# Main.net
KiCad netlist of a schematic drawn in Altium Designer
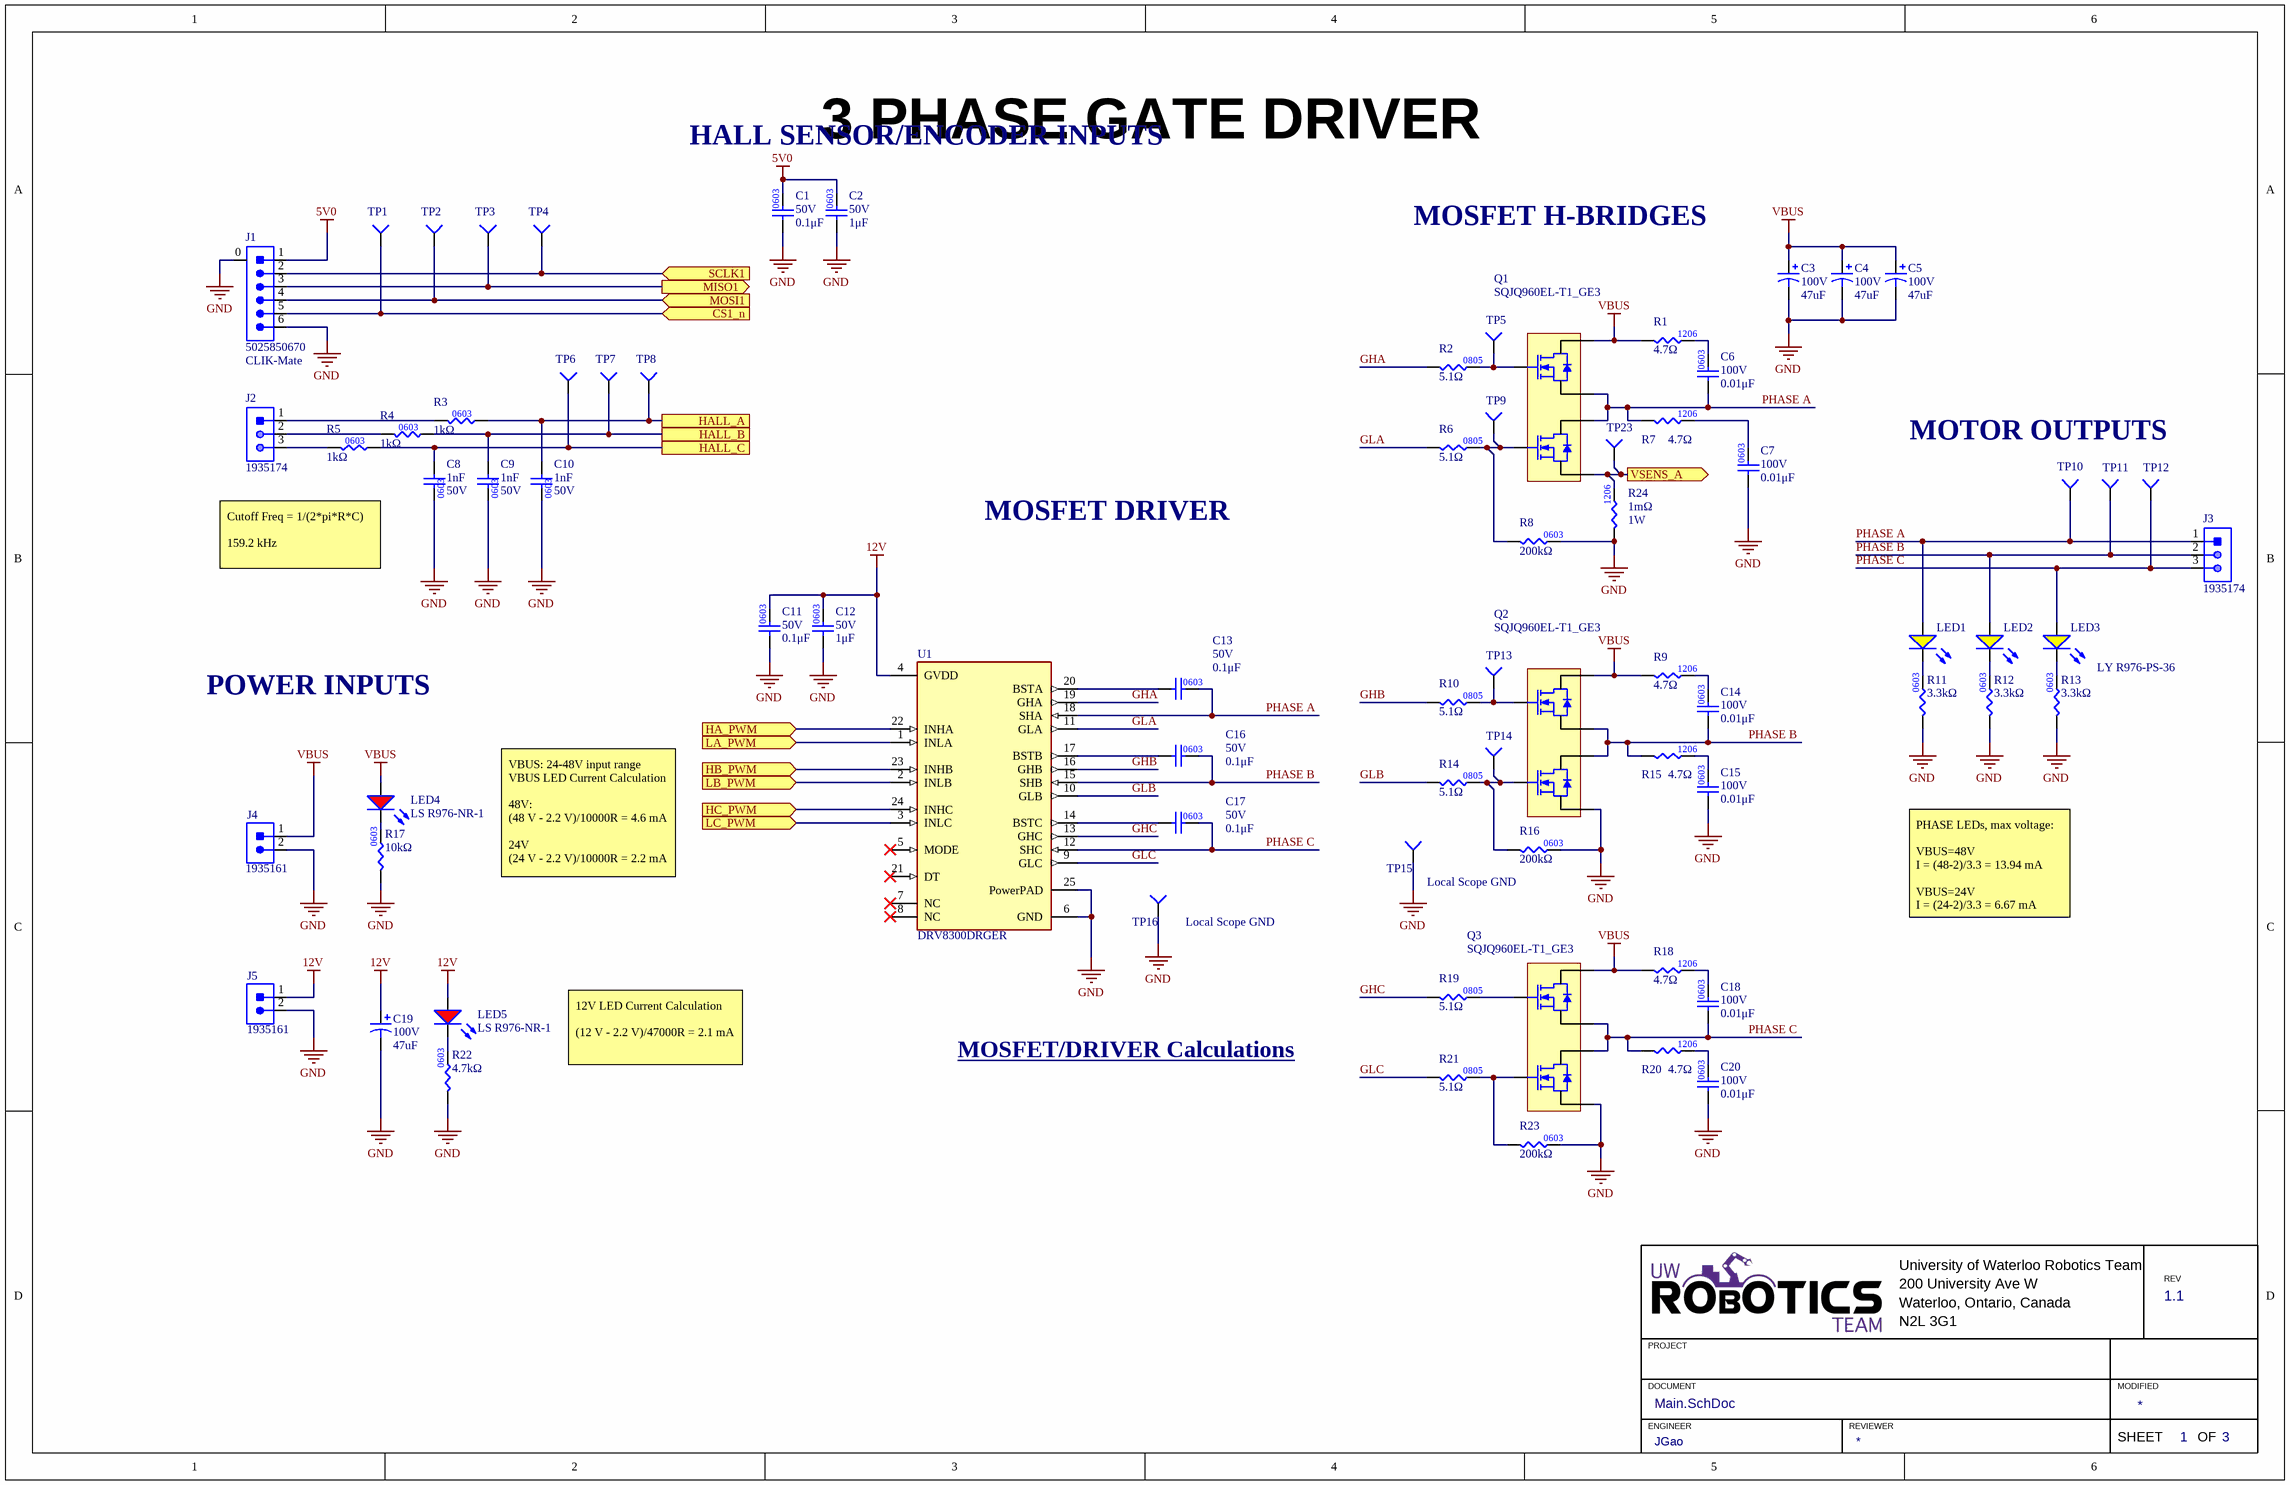
[diagram p0: Main.SchDoc]

(export (version "E")
  (design (tool "Eeschema 10.0.6"))
  (components
    (comp (ref "C1")
      (value "0.1μF")
      (footprint "CAP0603")
      (description "CAP CER 0.1UF 50V X7R 0603")
      (fields (field (name "VOLTAGE RATING") "50V") (field (name "Comment") "CAP_0.1uF_50V_0603"))
      (libsource (lib "UWRT_Schematic_Library_2020") (part "CAP_0.1uF_50V_0603"))
    )
    (comp (ref "C2")
      (value "1μF")
      (footprint "CAP0603")
      (description "CAP CER 1UF 50V X6S 0603")
      (fields (field (name "VOLTAGE RATING") "50V") (field (name "Comment") "CAP_1uF_50V_0603"))
      (libsource (lib "UWRT_Schematic_Library_2020") (part "CAP_1uF_50V_0603"))
    )
    (comp (ref "C3")
      (value "CAP_47uF_100V_ALUM")
      (footprint "RADIAL_CORNELL_D")
      (fields
        (field (name "MANUFACTURER") "Nichicon")
        (field (name "MANUFACTURER PART NUMBER") "UCD2A470MNQ1MS")
        (field (name "VOLTAGE RATING") "100V")
        (field (name "CAPACITANCE") "47uF")
      )
      (libsource (lib "UWRT_Schematic_Library_2020") (part "CAP_47uF_100V_ALUM"))
    )
    (comp (ref "C4")
      (value "CAP_47uF_100V_ALUM")
      (footprint "RADIAL_CORNELL_D")
      (fields
        (field (name "MANUFACTURER") "Nichicon")
        (field (name "MANUFACTURER PART NUMBER") "UCD2A470MNQ1MS")
        (field (name "VOLTAGE RATING") "100V")
        (field (name "CAPACITANCE") "47uF")
      )
      (libsource (lib "UWRT_Schematic_Library_2020") (part "CAP_47uF_100V_ALUM"))
    )
    (comp (ref "C5")
      (value "CAP_47uF_100V_ALUM")
      (footprint "RADIAL_CORNELL_D")
      (fields
        (field (name "MANUFACTURER") "Nichicon")
        (field (name "MANUFACTURER PART NUMBER") "UCD2A470MNQ1MS")
        (field (name "VOLTAGE RATING") "100V")
        (field (name "CAPACITANCE") "47uF")
      )
      (libsource (lib "UWRT_Schematic_Library_2020") (part "CAP_47uF_100V_ALUM"))
    )
    (comp (ref "C6")
      (value "0.01μF")
      (footprint "CAP0603")
      (description "CAP CER 0.01uF 100V X7R 0603")
      (fields (field (name "VOLTAGE RATING") "100V") (field (name "Comment") "CAP_0.01uF_100V_0603"))
      (libsource (lib "UWRT_Schematic_Library_2020") (part "CAP_0.01uF_100V_0603"))
    )
    (comp (ref "C7")
      (value "0.01μF")
      (footprint "CAP0603")
      (description "CAP CER 0.01uF 100V X7R 0603")
      (fields (field (name "VOLTAGE RATING") "100V") (field (name "Comment") "CAP_0.01uF_100V_0603"))
      (libsource (lib "UWRT_Schematic_Library_2020") (part "CAP_0.01uF_100V_0603"))
    )
    (comp (ref "C8")
      (value "1nF")
      (footprint "cap0603")
      (description "CAP CER 1NF 50V X7R 0603")
      (fields
        (field (name "MANUFACTURER") "KYOCERA AVX")
        (field (name "MANUFACTURER PART NUMBER") "06035C102KAT2A")
        (field (name "VOLTAGE RATING") "50V")
      )
      (libsource (lib "UWRT_Schematic_Library_2020") (part "CAP_1nF_50V_0603_XR7"))
    )
    (comp (ref "C9")
      (value "1nF")
      (footprint "cap0603")
      (description "CAP CER 1NF 50V X7R 0603")
      (fields
        (field (name "MANUFACTURER") "KYOCERA AVX")
        (field (name "MANUFACTURER PART NUMBER") "06035C102KAT2A")
        (field (name "VOLTAGE RATING") "50V")
      )
      (libsource (lib "UWRT_Schematic_Library_2020") (part "CAP_1nF_50V_0603_XR7"))
    )
    (comp (ref "C10")
      (value "1nF")
      (footprint "cap0603")
      (description "CAP CER 1NF 50V X7R 0603")
      (fields
        (field (name "MANUFACTURER") "KYOCERA AVX")
        (field (name "MANUFACTURER PART NUMBER") "06035C102KAT2A")
        (field (name "VOLTAGE RATING") "50V")
      )
      (libsource (lib "UWRT_Schematic_Library_2020") (part "CAP_1nF_50V_0603_XR7"))
    )
    (comp (ref "C11")
      (value "0.1μF")
      (footprint "CAP0603")
      (description "CAP CER 0.1UF 50V X7R 0603")
      (fields (field (name "VOLTAGE RATING") "50V") (field (name "Comment") "CAP_0.1uF_50V_0603"))
      (libsource (lib "UWRT_Schematic_Library_2020") (part "CAP_0.1uF_50V_0603"))
    )
    (comp (ref "C12")
      (value "1μF")
      (footprint "CAP0603")
      (description "CAP CER 1UF 50V X6S 0603")
      (fields (field (name "VOLTAGE RATING") "50V") (field (name "Comment") "CAP_1uF_50V_0603"))
      (libsource (lib "UWRT_Schematic_Library_2020") (part "CAP_1uF_50V_0603"))
    )
    (comp (ref "C13")
      (value "0.1μF")
      (footprint "CAP0603")
      (description "CAP CER 0.1UF 50V X7R 0603")
      (fields (field (name "VOLTAGE RATING") "50V") (field (name "Comment") "CAP_0.1uF_50V_0603"))
      (libsource (lib "UWRT_Schematic_Library_2020") (part "CAP_0.1uF_50V_0603"))
    )
    (comp (ref "C14")
      (value "0.01μF")
      (footprint "CAP0603")
      (description "CAP CER 0.01uF 100V X7R 0603")
      (fields (field (name "VOLTAGE RATING") "100V") (field (name "Comment") "CAP_0.01uF_100V_0603"))
      (libsource (lib "UWRT_Schematic_Library_2020") (part "CAP_0.01uF_100V_0603"))
    )
    (comp (ref "C15")
      (value "0.01μF")
      (footprint "CAP0603")
      (description "CAP CER 0.01uF 100V X7R 0603")
      (fields (field (name "VOLTAGE RATING") "100V") (field (name "Comment") "CAP_0.01uF_100V_0603"))
      (libsource (lib "UWRT_Schematic_Library_2020") (part "CAP_0.01uF_100V_0603"))
    )
    (comp (ref "C16")
      (value "0.1μF")
      (footprint "CAP0603")
      (description "CAP CER 0.1UF 50V X7R 0603")
      (fields (field (name "VOLTAGE RATING") "50V") (field (name "Comment") "CAP_0.1uF_50V_0603"))
      (libsource (lib "UWRT_Schematic_Library_2020") (part "CAP_0.1uF_50V_0603"))
    )
    (comp (ref "C17")
      (value "0.1μF")
      (footprint "CAP0603")
      (description "CAP CER 0.1UF 50V X7R 0603")
      (fields (field (name "VOLTAGE RATING") "50V") (field (name "Comment") "CAP_0.1uF_50V_0603"))
      (libsource (lib "UWRT_Schematic_Library_2020") (part "CAP_0.1uF_50V_0603"))
    )
    (comp (ref "C18")
      (value "0.01μF")
      (footprint "CAP0603")
      (description "CAP CER 0.01uF 100V X7R 0603")
      (fields (field (name "VOLTAGE RATING") "100V") (field (name "Comment") "CAP_0.01uF_100V_0603"))
      (libsource (lib "UWRT_Schematic_Library_2020") (part "CAP_0.01uF_100V_0603"))
    )
    (comp (ref "C19")
      (value "CAP_47uF_100V_ALUM")
      (footprint "RADIAL_CORNELL_D")
      (fields
        (field (name "MANUFACTURER") "Nichicon")
        (field (name "MANUFACTURER PART NUMBER") "UCD2A470MNQ1MS")
        (field (name "VOLTAGE RATING") "100V")
        (field (name "CAPACITANCE") "47uF")
      )
      (libsource (lib "UWRT_Schematic_Library_2020") (part "CAP_47uF_100V_ALUM"))
    )
    (comp (ref "C20")
      (value "0.01μF")
      (footprint "CAP0603")
      (description "CAP CER 0.01uF 100V X7R 0603")
      (fields (field (name "VOLTAGE RATING") "100V") (field (name "Comment") "CAP_0.01uF_100V_0603"))
      (libsource (lib "UWRT_Schematic_Library_2020") (part "CAP_0.01uF_100V_0603"))
    )
    (comp (ref "J1")
      (value "CON_6M_SM_RA_1.5mm")
      (footprint "MOLEX-5025850670")
      (description "CONN HEADER SMD RIGHT ANGLE 1.5 MM PITCH")
      (fields (field (name "MANUFACTURER PART NUMBER 1") "5025850670") (field (name "FAMILY") "CLIK-Mate"))
      (libsource (lib "UWRT_Schematic_Library_2020") (part "CON_6M_SM_RA_1.5mm"))
    )
    (comp (ref "J2")
      (value "CON_3POS_SCREW_TERM")
      (footprint "1935174")
      (description "TERM BLK 3POS SIDE ENTRY 5MM")
      (fields (field (name "MANUFACTURER PART NUMBER 1") "1935174"))
      (libsource (lib "UWRT_Schematic_Library_2020") (part "CON_3POS_SCREW_TERM"))
    )
    (comp (ref "J3")
      (value "CON_3POS_SCREW_TERM")
      (footprint "1935174")
      (description "TERM BLK 3POS SIDE ENTRY 5MM")
      (fields (field (name "MANUFACTURER PART NUMBER 1") "1935174"))
      (libsource (lib "") (part "CON_3POS_SCREW_TERM_1"))
    )
    (comp (ref "J4")
      (value "CON_2POS_SCREW_TERM")
      (footprint "1935161")
      (description "TERM BLK 2POS SIDE ENTRY 5MM")
      (fields (field (name "MANUFACTURER PART NUMBER 1") "1935161"))
      (libsource (lib "UWRT_Schematic_Library_2020") (part "CON_2POS_SCREW_TERM"))
    )
    (comp (ref "J5")
      (value "CON_2POS_SCREW_TERM")
      (footprint "1935161")
      (description "TERM BLK 2POS SIDE ENTRY 5MM")
      (fields (field (name "MANUFACTURER PART NUMBER 1") "1935161"))
      (libsource (lib "UWRT_Schematic_Library_2020") (part "CON_2POS_SCREW_TERM"))
    )
    (comp (ref "LED1")
      (value "LED_YELLOW")
      (footprint "LED_0805_YELLOW")
      (description "LED YELLOW DIFFUSED 0805 SMD")
      (fields (field (name "MANUFACTURER PART NUMBER 1") "LY R976-PS-36"))
      (libsource (lib "UWRT_Schematic_Library_2020") (part "LED_YELLOW"))
    )
    (comp (ref "LED2")
      (value "LED_YELLOW")
      (footprint "LED_0805_YELLOW")
      (description "LED YELLOW DIFFUSED 0805 SMD")
      (libsource (lib "UWRT_Schematic_Library_2020") (part "LED_YELLOW"))
    )
    (comp (ref "LED3")
      (value "LED_YELLOW")
      (footprint "LED_0805_YELLOW")
      (description "LED YELLOW DIFFUSED 0805 SMD")
      (libsource (lib "UWRT_Schematic_Library_2020") (part "LED_YELLOW"))
    )
    (comp (ref "LED4")
      (value "LED_RED")
      (footprint "LED_0805_RED")
      (description "LED RED DIFFUSED 0805 SMD")
      (fields (field (name "MANUFACTURER PART NUMBER 1") "LS R976-NR-1"))
      (libsource (lib "UWRT_Schematic_Library_2020") (part "LED_RED"))
    )
    (comp (ref "LED5")
      (value "LED_RED")
      (footprint "LED_0805_RED")
      (description "LED RED DIFFUSED 0805 SMD")
      (fields (field (name "MANUFACTURER PART NUMBER 1") "LS R976-NR-1"))
      (libsource (lib "UWRT_Schematic_Library_2020") (part "LED_RED"))
    )
    (comp (ref "Q1")
      (value "NMOS_2CH_60V_63A")
      (footprint "PowerPAK 8 x 8 Dual")
      (description "MOSFET 2 N-CH 60V POWERPAK8X8")
      (fields
        (field (name "MANUFACTURER") "Vishay")
        (field (name "MANUFACTURER PART NUMBER") "SQJQ960EL-T1_GE3")
      )
      (libsource (lib "UWRT_Schematic_Library_2020") (part "NMOS_2CH_60V_63A"))
    )
    (comp (ref "Q2")
      (value "NMOS_2CH_60V_63A")
      (footprint "PowerPAK 8 x 8 Dual")
      (description "MOSFET 2 N-CH 60V POWERPAK8X8")
      (fields
        (field (name "MANUFACTURER") "Vishay")
        (field (name "MANUFACTURER PART NUMBER") "SQJQ960EL-T1_GE3")
      )
      (libsource (lib "UWRT_Schematic_Library_2020") (part "NMOS_2CH_60V_63A"))
    )
    (comp (ref "Q3")
      (value "NMOS_2CH_60V_63A")
      (footprint "PowerPAK 8 x 8 Dual")
      (description "MOSFET 2 N-CH 60V POWERPAK8X8")
      (fields
        (field (name "MANUFACTURER") "Vishay")
        (field (name "MANUFACTURER PART NUMBER") "SQJQ960EL-T1_GE3")
      )
      (libsource (lib "UWRT_Schematic_Library_2020") (part "NMOS_2CH_60V_63A"))
    )
    (comp (ref "R1")
      (value "4.7Ω")
      (footprint "RES1206")
      (description "RES 4.7 OHM 1% 1/2W 1206")
      (fields (field (name "Comment") "RES_4.7Ω_1206_1%"))
      (libsource (lib "UWRT_Schematic_Library_2020") (part "RES_4.7Ω_1206_1%"))
    )
    (comp (ref "R2")
      (value "5.1Ω")
      (footprint "RES0805")
      (description "RES 5.1 OHM 5% 1/8W 0805")
      (fields (field (name "Comment") "RES_5.1Ω_0805_5%"))
      (libsource (lib "UWRT_Schematic_Library_2020") (part "RES_5.1Ω_0805_5%"))
    )
    (comp (ref "R3")
      (value "1kΩ")
      (footprint "RES0603")
      (description "RES 1K OHM 5% 1/10W 0603")
      (fields (field (name "Comment") "RES_1kΩ_0603_5%"))
      (libsource (lib "UWRT_Schematic_Library_2020") (part "RES_1kΩ_0603_5%"))
    )
    (comp (ref "R4")
      (value "1kΩ")
      (footprint "RES0603")
      (description "RES 1K OHM 5% 1/10W 0603")
      (fields (field (name "Comment") "RES_1kΩ_0603_5%"))
      (libsource (lib "UWRT_Schematic_Library_2020") (part "RES_1kΩ_0603_5%"))
    )
    (comp (ref "R5")
      (value "1kΩ")
      (footprint "RES0603")
      (description "RES 1K OHM 5% 1/10W 0603")
      (fields (field (name "Comment") "RES_1kΩ_0603_5%"))
      (libsource (lib "UWRT_Schematic_Library_2020") (part "RES_1kΩ_0603_5%"))
    )
    (comp (ref "R6")
      (value "5.1Ω")
      (footprint "RES0805")
      (description "RES 5.1 OHM 5% 1/8W 0805")
      (fields (field (name "Comment") "RES_5.1Ω_0805_5%"))
      (libsource (lib "UWRT_Schematic_Library_2020") (part "RES_5.1Ω_0805_5%"))
    )
    (comp (ref "R7")
      (value "4.7Ω")
      (footprint "RES1206")
      (description "RES 4.7 OHM 1% 1/2W 1206")
      (fields (field (name "Comment") "RES_4.7Ω_1206_1%"))
      (libsource (lib "UWRT_Schematic_Library_2020") (part "RES_4.7Ω_1206_1%"))
    )
    (comp (ref "R8")
      (value "200kΩ")
      (footprint "RES0603")
      (description "RES 200K OHM 5% 1/10W 0603")
      (fields (field (name "Comment") "RES_200kΩ_0603_5%"))
      (libsource (lib "UWRT_Schematic_Library_2020") (part "RES_200kΩ_0603_5%"))
    )
    (comp (ref "R9")
      (value "4.7Ω")
      (footprint "RES1206")
      (description "RES 4.7 OHM 1% 1/2W 1206")
      (fields (field (name "Comment") "RES_4.7Ω_1206_1%"))
      (libsource (lib "UWRT_Schematic_Library_2020") (part "RES_4.7Ω_1206_1%"))
    )
    (comp (ref "R10")
      (value "5.1Ω")
      (footprint "RES0805")
      (description "RES 5.1 OHM 5% 1/8W 0805")
      (fields (field (name "Comment") "RES_5.1Ω_0805_5%"))
      (libsource (lib "UWRT_Schematic_Library_2020") (part "RES_5.1Ω_0805_5%"))
    )
    (comp (ref "R11")
      (value "3.3kΩ")
      (footprint "RES0603")
      (description "RES 3.3K OHM 1% 1/10W 0603")
      (fields (field (name "Comment") "RES_3.3kΩ_0603_1%"))
      (libsource (lib "UWRT_Schematic_Library_2020") (part "RES_3.3kΩ_0603_1%"))
    )
    (comp (ref "R12")
      (value "3.3kΩ")
      (footprint "RES0603")
      (description "RES 3.3K OHM 1% 1/10W 0603")
      (fields (field (name "Comment") "RES_3.3kΩ_0603_1%"))
      (libsource (lib "UWRT_Schematic_Library_2020") (part "RES_3.3kΩ_0603_1%"))
    )
    (comp (ref "R13")
      (value "3.3kΩ")
      (footprint "RES0603")
      (description "RES 3.3K OHM 1% 1/10W 0603")
      (fields (field (name "Comment") "RES_3.3kΩ_0603_1%"))
      (libsource (lib "UWRT_Schematic_Library_2020") (part "RES_3.3kΩ_0603_1%"))
    )
    (comp (ref "R14")
      (value "5.1Ω")
      (footprint "RES0805")
      (description "RES 5.1 OHM 5% 1/8W 0805")
      (fields (field (name "Comment") "RES_5.1Ω_0805_5%"))
      (libsource (lib "UWRT_Schematic_Library_2020") (part "RES_5.1Ω_0805_5%"))
    )
    (comp (ref "R15")
      (value "4.7Ω")
      (footprint "RES1206")
      (description "RES 4.7 OHM 1% 1/2W 1206")
      (fields (field (name "Comment") "RES_4.7Ω_1206_1%"))
      (libsource (lib "UWRT_Schematic_Library_2020") (part "RES_4.7Ω_1206_1%"))
    )
    (comp (ref "R16")
      (value "200kΩ")
      (footprint "RES0603")
      (description "RES 200K OHM 5% 1/10W 0603")
      (fields (field (name "Comment") "RES_200kΩ_0603_5%"))
      (libsource (lib "UWRT_Schematic_Library_2020") (part "RES_200kΩ_0603_5%"))
    )
    (comp (ref "R17")
      (value "10kΩ")
      (footprint "RES0603")
      (description "RES 10K OHM 5% 1/10W 0603")
      (fields (field (name "Comment") "RES_10kΩ_0603_5%"))
      (libsource (lib "UWRT_Schematic_Library_2020") (part "RES_10kΩ_0603_5%"))
    )
    (comp (ref "R18")
      (value "4.7Ω")
      (footprint "RES1206")
      (description "RES 4.7 OHM 1% 1/2W 1206")
      (fields (field (name "Comment") "RES_4.7Ω_1206_1%"))
      (libsource (lib "UWRT_Schematic_Library_2020") (part "RES_4.7Ω_1206_1%"))
    )
    (comp (ref "R19")
      (value "5.1Ω")
      (footprint "RES0805")
      (description "RES 5.1 OHM 5% 1/8W 0805")
      (fields (field (name "Comment") "RES_5.1Ω_0805_5%"))
      (libsource (lib "UWRT_Schematic_Library_2020") (part "RES_5.1Ω_0805_5%"))
    )
    (comp (ref "R20")
      (value "4.7Ω")
      (footprint "RES1206")
      (description "RES 4.7 OHM 1% 1/2W 1206")
      (fields (field (name "Comment") "RES_4.7Ω_1206_1%"))
      (libsource (lib "UWRT_Schematic_Library_2020") (part "RES_4.7Ω_1206_1%"))
    )
    (comp (ref "R21")
      (value "5.1Ω")
      (footprint "RES0805")
      (description "RES 5.1 OHM 5% 1/8W 0805")
      (fields (field (name "Comment") "RES_5.1Ω_0805_5%"))
      (libsource (lib "UWRT_Schematic_Library_2020") (part "RES_5.1Ω_0805_5%"))
    )
    (comp (ref "R22")
      (value "4.7kΩ")
      (footprint "RES0603")
      (description "RES 4.7K OHM 5% 1/10W 0603")
      (fields (field (name "Comment") "RES_4.7kΩ_0603_5%"))
      (libsource (lib "UWRT_Schematic_Library_2020") (part "RES_4.7kΩ_0603_5%"))
    )
    (comp (ref "R23")
      (value "200kΩ")
      (footprint "RES0603")
      (description "RES 200K OHM 5% 1/10W 0603")
      (fields (field (name "Comment") "RES_200kΩ_0603_5%"))
      (libsource (lib "UWRT_Schematic_Library_2020") (part "RES_200kΩ_0603_5%"))
    )
    (comp (ref "R24")
      (value "1mΩ")
      (footprint "RESC160320X70-RL1632T4F-R001-FNH")
      (description "RES 0.001 OHM 1% 1W 1206")
      (fields (field (name "Comment") "RES_1mΩ_1206_1%"))
      (libsource (lib "UWRT_Schematic_Library_2020") (part "RES_1mΩ_1206_1%"))
    )
    (comp (ref "TP1")
      (value "TESTPOINT_1MM_CIRCLE")
      (footprint "TESTPOINT_CIRCLE_1MM")
      (description "TESTPOINT 1MM CIRCLE")
      (libsource (lib "UWRT_Schematic_Library_2020") (part "TESTPOINT_1MM_CIRCLE"))
    )
    (comp (ref "TP2")
      (value "TESTPOINT_1MM_CIRCLE")
      (footprint "TESTPOINT_CIRCLE_1MM")
      (description "TESTPOINT 1MM CIRCLE")
      (libsource (lib "UWRT_Schematic_Library_2020") (part "TESTPOINT_1MM_CIRCLE"))
    )
    (comp (ref "TP3")
      (value "TESTPOINT_1MM_CIRCLE")
      (footprint "TESTPOINT_CIRCLE_1MM")
      (description "TESTPOINT 1MM CIRCLE")
      (libsource (lib "UWRT_Schematic_Library_2020") (part "TESTPOINT_1MM_CIRCLE"))
    )
    (comp (ref "TP4")
      (value "TESTPOINT_1MM_CIRCLE")
      (footprint "TESTPOINT_CIRCLE_1MM")
      (description "TESTPOINT 1MM CIRCLE")
      (libsource (lib "UWRT_Schematic_Library_2020") (part "TESTPOINT_1MM_CIRCLE"))
    )
    (comp (ref "TP5")
      (value "TESTPOINT_1MM_CIRCLE")
      (footprint "TESTPOINT_CIRCLE_1MM")
      (description "TESTPOINT 1MM CIRCLE")
      (libsource (lib "UWRT_Schematic_Library_2020") (part "TESTPOINT_1MM_CIRCLE"))
    )
    (comp (ref "TP6")
      (value "TESTPOINT_1MM_CIRCLE")
      (footprint "TESTPOINT_CIRCLE_1MM")
      (description "TESTPOINT 1MM CIRCLE")
      (libsource (lib "UWRT_Schematic_Library_2020") (part "TESTPOINT_1MM_CIRCLE"))
    )
    (comp (ref "TP7")
      (value "TESTPOINT_1MM_CIRCLE")
      (footprint "TESTPOINT_CIRCLE_1MM")
      (description "TESTPOINT 1MM CIRCLE")
      (libsource (lib "UWRT_Schematic_Library_2020") (part "TESTPOINT_1MM_CIRCLE"))
    )
    (comp (ref "TP8")
      (value "TESTPOINT_1MM_CIRCLE")
      (footprint "TESTPOINT_CIRCLE_1MM")
      (description "TESTPOINT 1MM CIRCLE")
      (libsource (lib "UWRT_Schematic_Library_2020") (part "TESTPOINT_1MM_CIRCLE"))
    )
    (comp (ref "TP9")
      (value "TESTPOINT_1MM_CIRCLE")
      (footprint "TESTPOINT_CIRCLE_1MM")
      (description "TESTPOINT 1MM CIRCLE")
      (libsource (lib "UWRT_Schematic_Library_2020") (part "TESTPOINT_1MM_CIRCLE"))
    )
    (comp (ref "TP10")
      (value "TESTPOINT_1MM_CIRCLE")
      (footprint "TESTPOINT_CIRCLE_1MM")
      (description "TESTPOINT 1MM CIRCLE")
      (libsource (lib "UWRT_Schematic_Library_2020") (part "TESTPOINT_1MM_CIRCLE"))
    )
    (comp (ref "TP11")
      (value "TESTPOINT_1MM_CIRCLE")
      (footprint "TESTPOINT_CIRCLE_1MM")
      (description "TESTPOINT 1MM CIRCLE")
      (libsource (lib "UWRT_Schematic_Library_2020") (part "TESTPOINT_1MM_CIRCLE"))
    )
    (comp (ref "TP12")
      (value "TESTPOINT_1MM_CIRCLE")
      (footprint "TESTPOINT_CIRCLE_1MM")
      (description "TESTPOINT 1MM CIRCLE")
      (libsource (lib "UWRT_Schematic_Library_2020") (part "TESTPOINT_1MM_CIRCLE"))
    )
    (comp (ref "TP13")
      (value "TESTPOINT_1MM_CIRCLE")
      (footprint "TESTPOINT_CIRCLE_1MM")
      (description "TESTPOINT 1MM CIRCLE")
      (libsource (lib "UWRT_Schematic_Library_2020") (part "TESTPOINT_1MM_CIRCLE"))
    )
    (comp (ref "TP14")
      (value "TESTPOINT_1MM_CIRCLE")
      (footprint "TESTPOINT_CIRCLE_1MM")
      (description "TESTPOINT 1MM CIRCLE")
      (libsource (lib "UWRT_Schematic_Library_2020") (part "TESTPOINT_1MM_CIRCLE"))
    )
    (comp (ref "TP15")
      (value "TESTPOINT_SMD_LOOP")
      (footprint "S1751-46R")
      (description "TESTPOINT SMD LOOP")
      (libsource (lib "UWRT_Schematic_Library_2020") (part "TESTPOINT_SMD_LOOP"))
    )
    (comp (ref "TP16")
      (value "TESTPOINT_SMD_LOOP")
      (footprint "S1751-46R")
      (description "TESTPOINT SMD LOOP")
      (libsource (lib "UWRT_Schematic_Library_2020") (part "TESTPOINT_SMD_LOOP"))
    )
    (comp (ref "TP23")
      (value "TESTPOINT_1MM_CIRCLE")
      (footprint "TESTPOINT_CIRCLE_1MM")
      (description "TESTPOINT 1MM CIRCLE")
      (libsource (lib "UWRT_Schematic_Library_2020") (part "TESTPOINT_1MM_CIRCLE"))
    )
    (comp (ref "U1")
      (value "DRV8300DRGER")
      (footprint "RGE0024B-IPC_B")
      (description "High-Side and Low-Side Gate Driver IC Non-Inverting 24-VQFN (4x4)")
      (fields (field (name "COPYRIGHT") "Copyright (C) 2022 Ultra Librarian. All rights reserved."))
      (libsource (lib "UWRT_Schematic_Library_2020") (part "DRV8300DRGER"))
    )
  )
  (nets
    (net (code "1") (name "/CS1_n") (class "Default")
      (node (ref "J1") (pin "5") (pinfunction "5_5") (pintype "passive"))
      (node (ref "TP1") (pin "1") (pinfunction "=value_1") (pintype "passive"))
    )
    (net (code "2") (name "/GHA") (class "Default")
      (node (ref "R2") (pin "1") (pinfunction "1_1") (pintype "passive"))
      (node (ref "U1") (pin "19") (pinfunction "GHA_19") (pintype "output"))
    )
    (net (code "3") (name "/GHB") (class "Default")
      (node (ref "R10") (pin "1") (pinfunction "1_1") (pintype "passive"))
      (node (ref "U1") (pin "16") (pinfunction "GHB_16") (pintype "output"))
    )
    (net (code "4") (name "/GHC") (class "Default")
      (node (ref "R19") (pin "1") (pinfunction "1_1") (pintype "passive"))
      (node (ref "U1") (pin "13") (pinfunction "GHC_13") (pintype "output"))
    )
    (net (code "5") (name "/GLA") (class "Default")
      (node (ref "R6") (pin "1") (pinfunction "1_1") (pintype "passive"))
      (node (ref "U1") (pin "11") (pinfunction "GLA_11") (pintype "output"))
    )
    (net (code "6") (name "/GLB") (class "Default")
      (node (ref "R14") (pin "1") (pinfunction "1_1") (pintype "passive"))
      (node (ref "U1") (pin "10") (pinfunction "GLB_10") (pintype "output"))
    )
    (net (code "7") (name "/GLC") (class "Default")
      (node (ref "R21") (pin "1") (pinfunction "1_1") (pintype "passive"))
      (node (ref "U1") (pin "9") (pinfunction "GLC_9") (pintype "output"))
    )
    (net (code "8") (name "/HALL_A") (class "Default")
      (node (ref "C10") (pin "2") (pinfunction "2_2") (pintype "passive"))
      (node (ref "R3") (pin "1") (pinfunction "1_1") (pintype "passive"))
      (node (ref "TP8") (pin "1") (pinfunction "=value_1") (pintype "passive"))
    )
    (net (code "9") (name "/HALL_B") (class "Default")
      (node (ref "C9") (pin "2") (pinfunction "2_2") (pintype "passive"))
      (node (ref "R4") (pin "1") (pinfunction "1_1") (pintype "passive"))
      (node (ref "TP7") (pin "1") (pinfunction "=value_1") (pintype "passive"))
    )
    (net (code "10") (name "/HALL_C") (class "Default")
      (node (ref "C8") (pin "2") (pinfunction "2_2") (pintype "passive"))
      (node (ref "R5") (pin "1") (pinfunction "1_1") (pintype "passive"))
      (node (ref "TP6") (pin "1") (pinfunction "=value_1") (pintype "passive"))
    )
    (net (code "11") (name "/HA_PWM") (class "Default")
      (node (ref "U1") (pin "22") (pinfunction "INHA_22") (pintype "input"))
    )
    (net (code "12") (name "/HB_PWM") (class "Default")
      (node (ref "U1") (pin "23") (pinfunction "INHB_23") (pintype "input"))
    )
    (net (code "13") (name "/HC_PWM") (class "Default")
      (node (ref "U1") (pin "24") (pinfunction "INHC_24") (pintype "input"))
    )
    (net (code "14") (name "/LA_PWM") (class "Default")
      (node (ref "U1") (pin "1") (pinfunction "INLA_1") (pintype "input"))
    )
    (net (code "15") (name "/LB_PWM") (class "Default")
      (node (ref "U1") (pin "2") (pinfunction "INLB_2") (pintype "input"))
    )
    (net (code "16") (name "/LC_PWM") (class "Default")
      (node (ref "U1") (pin "3") (pinfunction "INLC_3") (pintype "input"))
    )
    (net (code "17") (name "/MISO1") (class "Default")
      (node (ref "J1") (pin "3") (pinfunction "3_3") (pintype "passive"))
      (node (ref "TP3") (pin "1") (pinfunction "=value_1") (pintype "passive"))
    )
    (net (code "18") (name "/MOSI1") (class "Default")
      (node (ref "J1") (pin "4") (pinfunction "4_4") (pintype "passive"))
      (node (ref "TP2") (pin "1") (pinfunction "=value_1") (pintype "passive"))
    )
    (net (code "19") (name "/PHASE A") (class "Default")
      (node (ref "C13") (pin "2") (pinfunction "2_2") (pintype "passive"))
      (node (ref "C6") (pin "1") (pinfunction "1_1") (pintype "passive"))
      (node (ref "J3") (pin "1") (pinfunction "1_1") (pintype "passive"))
      (node (ref "LED1") (pin "1") (pinfunction "A_1") (pintype "passive"))
      (node (ref "Q1") (pin "2") (pinfunction "S1_2") (pintype "passive"))
      (node (ref "Q1") (pin "6") (pinfunction "D2_6") (pintype "passive"))
      (node (ref "R7") (pin "1") (pinfunction "1_1") (pintype "passive"))
      (node (ref "TP10") (pin "1") (pinfunction "=value_1") (pintype "passive"))
      (node (ref "U1") (pin "18") (pinfunction "SHA_18") (pintype "input"))
    )
    (net (code "20") (name "/PHASE B") (class "Default")
      (node (ref "C14") (pin "1") (pinfunction "1_1") (pintype "passive"))
      (node (ref "C16") (pin "2") (pinfunction "2_2") (pintype "passive"))
      (node (ref "J3") (pin "2") (pinfunction "2_2") (pintype "passive"))
      (node (ref "LED2") (pin "1") (pinfunction "A_1") (pintype "passive"))
      (node (ref "Q2") (pin "2") (pinfunction "S1_2") (pintype "passive"))
      (node (ref "Q2") (pin "6") (pinfunction "D2_6") (pintype "passive"))
      (node (ref "R15") (pin "1") (pinfunction "1_1") (pintype "passive"))
      (node (ref "TP11") (pin "1") (pinfunction "=value_1") (pintype "passive"))
      (node (ref "U1") (pin "15") (pinfunction "SHB_15") (pintype "input"))
    )
    (net (code "21") (name "/PHASE C") (class "Default")
      (node (ref "C17") (pin "2") (pinfunction "2_2") (pintype "passive"))
      (node (ref "C18") (pin "1") (pinfunction "1_1") (pintype "passive"))
      (node (ref "J3") (pin "3") (pinfunction "3_3") (pintype "passive"))
      (node (ref "LED3") (pin "1") (pinfunction "A_1") (pintype "passive"))
      (node (ref "Q3") (pin "2") (pinfunction "S1_2") (pintype "passive"))
      (node (ref "Q3") (pin "6") (pinfunction "D2_6") (pintype "passive"))
      (node (ref "R20") (pin "1") (pinfunction "1_1") (pintype "passive"))
      (node (ref "TP12") (pin "1") (pinfunction "=value_1") (pintype "passive"))
      (node (ref "U1") (pin "12") (pinfunction "SHC_12") (pintype "input"))
    )
    (net (code "22") (name "/SCLK1") (class "Default")
      (node (ref "J1") (pin "2") (pinfunction "2_2") (pintype "passive"))
      (node (ref "TP4") (pin "1") (pinfunction "=value_1") (pintype "passive"))
    )
    (net (code "23") (name "/VSENS_A") (class "Default")
      (node (ref "Q1") (pin "3") (pinfunction "S2_3") (pintype "passive"))
      (node (ref "R24") (pin "2") (pinfunction "2_2") (pintype "passive"))
      (node (ref "TP23") (pin "1") (pinfunction "=value_1") (pintype "passive"))
    )
    (net (code "24") (name "5V0") (class "Default")
      (node (ref "C1") (pin "2") (pinfunction "2_2") (pintype "passive"))
      (node (ref "C2") (pin "2") (pinfunction "2_2") (pintype "passive"))
      (node (ref "J1") (pin "1") (pinfunction "1_1") (pintype "passive"))
    )
    (net (code "25") (name "12V") (class "Default")
      (node (ref "C11") (pin "2") (pinfunction "2_2") (pintype "passive"))
      (node (ref "C12") (pin "2") (pinfunction "2_2") (pintype "passive"))
      (node (ref "C19") (pin "1") (pinfunction "1_1") (pintype "passive"))
      (node (ref "J5") (pin "1") (pinfunction "1_1") (pintype "passive"))
      (node (ref "LED5") (pin "1") (pinfunction "A_1") (pintype "passive"))
      (node (ref "U1") (pin "4") (pinfunction "GVDD_4") (pintype "power_in"))
    )
    (net (code "26") (name "GND") (class "Default")
      (node (ref "C1") (pin "1") (pinfunction "1_1") (pintype "passive"))
      (node (ref "C10") (pin "1") (pinfunction "1_1") (pintype "passive"))
      (node (ref "C11") (pin "1") (pinfunction "1_1") (pintype "passive"))
      (node (ref "C12") (pin "1") (pinfunction "1_1") (pintype "passive"))
      (node (ref "C15") (pin "1") (pinfunction "1_1") (pintype "passive"))
      (node (ref "C19") (pin "2") (pinfunction "2_2") (pintype "passive"))
      (node (ref "C2") (pin "1") (pinfunction "1_1") (pintype "passive"))
      (node (ref "C20") (pin "1") (pinfunction "1_1") (pintype "passive"))
      (node (ref "C3") (pin "2") (pinfunction "2_2") (pintype "passive"))
      (node (ref "C4") (pin "2") (pinfunction "2_2") (pintype "passive"))
      (node (ref "C5") (pin "2") (pinfunction "2_2") (pintype "passive"))
      (node (ref "C7") (pin "1") (pinfunction "1_1") (pintype "passive"))
      (node (ref "C8") (pin "1") (pinfunction "1_1") (pintype "passive"))
      (node (ref "C9") (pin "1") (pinfunction "1_1") (pintype "passive"))
      (node (ref "J1") (pin "0") (pinfunction "0_0") (pintype "passive"))
      (node (ref "J1") (pin "6") (pinfunction "6_6") (pintype "passive"))
      (node (ref "J4") (pin "2") (pinfunction "2_2") (pintype "passive"))
      (node (ref "J5") (pin "2") (pinfunction "2_2") (pintype "passive"))
      (node (ref "Q2") (pin "3") (pinfunction "S2_3") (pintype "passive"))
      (node (ref "Q3") (pin "3") (pinfunction "S2_3") (pintype "passive"))
      (node (ref "R11") (pin "1") (pinfunction "1_1") (pintype "passive"))
      (node (ref "R12") (pin "1") (pinfunction "1_1") (pintype "passive"))
      (node (ref "R13") (pin "1") (pinfunction "1_1") (pintype "passive"))
      (node (ref "R16") (pin "2") (pinfunction "2_2") (pintype "passive"))
      (node (ref "R17") (pin "1") (pinfunction "1_1") (pintype "passive"))
      (node (ref "R22") (pin "1") (pinfunction "1_1") (pintype "passive"))
      (node (ref "R23") (pin "2") (pinfunction "2_2") (pintype "passive"))
      (node (ref "R24") (pin "1") (pinfunction "1_1") (pintype "passive"))
      (node (ref "R8") (pin "2") (pinfunction "2_2") (pintype "passive"))
      (node (ref "TP15") (pin "1") (pinfunction "=value_1") (pintype "passive"))
      (node (ref "TP16") (pin "1") (pinfunction "=value_1") (pintype "passive"))
      (node (ref "U1") (pin "25") (pinfunction "PowerPAD_25") (pintype "power_in"))
      (node (ref "U1") (pin "6") (pinfunction "GND_6") (pintype "power_in"))
    )
    (net (code "27") (name "Net-(C6-Pad2)") (class "Default")
      (node (ref "C6") (pin "2") (pinfunction "2_2") (pintype "passive"))
      (node (ref "R1") (pin "2") (pinfunction "2_2") (pintype "passive"))
    )
    (net (code "28") (name "Net-(C7-Pad2)") (class "Default")
      (node (ref "C7") (pin "2") (pinfunction "2_2") (pintype "passive"))
      (node (ref "R7") (pin "2") (pinfunction "2_2") (pintype "passive"))
    )
    (net (code "29") (name "Net-(C14-Pad2)") (class "Default")
      (node (ref "C14") (pin "2") (pinfunction "2_2") (pintype "passive"))
      (node (ref "R9") (pin "2") (pinfunction "2_2") (pintype "passive"))
    )
    (net (code "30") (name "Net-(C15-Pad2)") (class "Default")
      (node (ref "C15") (pin "2") (pinfunction "2_2") (pintype "passive"))
      (node (ref "R15") (pin "2") (pinfunction "2_2") (pintype "passive"))
    )
    (net (code "31") (name "Net-(C18-Pad2)") (class "Default")
      (node (ref "C18") (pin "2") (pinfunction "2_2") (pintype "passive"))
      (node (ref "R18") (pin "2") (pinfunction "2_2") (pintype "passive"))
    )
    (net (code "32") (name "Net-(C20-Pad2)") (class "Default")
      (node (ref "C20") (pin "2") (pinfunction "2_2") (pintype "passive"))
      (node (ref "R20") (pin "2") (pinfunction "2_2") (pintype "passive"))
    )
    (net (code "33") (name "Net-(J2-Pad1)") (class "Default")
      (node (ref "J2") (pin "1") (pinfunction "1_1") (pintype "passive"))
      (node (ref "R3") (pin "2") (pinfunction "2_2") (pintype "passive"))
    )
    (net (code "34") (name "Net-(J2-Pad2)") (class "Default")
      (node (ref "J2") (pin "2") (pinfunction "2_2") (pintype "passive"))
      (node (ref "R4") (pin "2") (pinfunction "2_2") (pintype "passive"))
    )
    (net (code "35") (name "Net-(J2-Pad3)") (class "Default")
      (node (ref "J2") (pin "3") (pinfunction "3_3") (pintype "passive"))
      (node (ref "R5") (pin "2") (pinfunction "2_2") (pintype "passive"))
    )
    (net (code "36") (name "Net-(LED1-K)") (class "Default")
      (node (ref "LED1") (pin "2") (pinfunction "K_2") (pintype "passive"))
      (node (ref "R11") (pin "2") (pinfunction "2_2") (pintype "passive"))
    )
    (net (code "37") (name "Net-(LED2-K)") (class "Default")
      (node (ref "LED2") (pin "2") (pinfunction "K_2") (pintype "passive"))
      (node (ref "R12") (pin "2") (pinfunction "2_2") (pintype "passive"))
    )
    (net (code "38") (name "Net-(LED3-K)") (class "Default")
      (node (ref "LED3") (pin "2") (pinfunction "K_2") (pintype "passive"))
      (node (ref "R13") (pin "2") (pinfunction "2_2") (pintype "passive"))
    )
    (net (code "39") (name "Net-(LED4-K)") (class "Default")
      (node (ref "LED4") (pin "2") (pinfunction "K_2") (pintype "passive"))
      (node (ref "R17") (pin "2") (pinfunction "2_2") (pintype "passive"))
    )
    (net (code "40") (name "Net-(LED5-K)") (class "Default")
      (node (ref "LED5") (pin "2") (pinfunction "K_2") (pintype "passive"))
      (node (ref "R22") (pin "2") (pinfunction "2_2") (pintype "passive"))
    )
    (net (code "41") (name "Net-(Q1-G1)") (class "Default")
      (node (ref "Q1") (pin "1") (pinfunction "G1_1") (pintype "passive"))
      (node (ref "R2") (pin "2") (pinfunction "2_2") (pintype "passive"))
      (node (ref "TP5") (pin "1") (pinfunction "=value_1") (pintype "passive"))
    )
    (net (code "42") (name "Net-(Q1-G2)") (class "Default")
      (node (ref "Q1") (pin "4") (pinfunction "G2_4") (pintype "passive"))
      (node (ref "R6") (pin "2") (pinfunction "2_2") (pintype "passive"))
      (node (ref "R8") (pin "1") (pinfunction "1_1") (pintype "passive"))
      (node (ref "TP9") (pin "1") (pinfunction "=value_1") (pintype "passive"))
    )
    (net (code "43") (name "Net-(Q2-G1)") (class "Default")
      (node (ref "Q2") (pin "1") (pinfunction "G1_1") (pintype "passive"))
      (node (ref "R10") (pin "2") (pinfunction "2_2") (pintype "passive"))
      (node (ref "TP13") (pin "1") (pinfunction "=value_1") (pintype "passive"))
    )
    (net (code "44") (name "Net-(Q2-G2)") (class "Default")
      (node (ref "Q2") (pin "4") (pinfunction "G2_4") (pintype "passive"))
      (node (ref "R14") (pin "2") (pinfunction "2_2") (pintype "passive"))
      (node (ref "R16") (pin "1") (pinfunction "1_1") (pintype "passive"))
      (node (ref "TP14") (pin "1") (pinfunction "=value_1") (pintype "passive"))
    )
    (net (code "45") (name "Net-(Q3-G1)") (class "Default")
      (node (ref "Q3") (pin "1") (pinfunction "G1_1") (pintype "passive"))
      (node (ref "R19") (pin "2") (pinfunction "2_2") (pintype "passive"))
    )
    (net (code "46") (name "Net-(Q3-G2)") (class "Default")
      (node (ref "Q3") (pin "4") (pinfunction "G2_4") (pintype "passive"))
      (node (ref "R21") (pin "2") (pinfunction "2_2") (pintype "passive"))
      (node (ref "R23") (pin "1") (pinfunction "1_1") (pintype "passive"))
    )
    (net (code "47") (name "Net-(U1-BSTA)") (class "Default")
      (node (ref "C13") (pin "1") (pinfunction "1_1") (pintype "passive"))
      (node (ref "U1") (pin "20") (pinfunction "BSTA_20") (pintype "output"))
    )
    (net (code "48") (name "Net-(U1-BSTB)") (class "Default")
      (node (ref "C16") (pin "1") (pinfunction "1_1") (pintype "passive"))
      (node (ref "U1") (pin "17") (pinfunction "BSTB_17") (pintype "output"))
    )
    (net (code "49") (name "Net-(U1-BSTC)") (class "Default")
      (node (ref "C17") (pin "1") (pinfunction "1_1") (pintype "passive"))
      (node (ref "U1") (pin "14") (pinfunction "BSTC_14") (pintype "output"))
    )
    (net (code "50") (name "VBUS") (class "Default")
      (node (ref "C3") (pin "1") (pinfunction "1_1") (pintype "passive"))
      (node (ref "C4") (pin "1") (pinfunction "1_1") (pintype "passive"))
      (node (ref "C5") (pin "1") (pinfunction "1_1") (pintype "passive"))
      (node (ref "J4") (pin "1") (pinfunction "1_1") (pintype "passive"))
      (node (ref "LED4") (pin "1") (pinfunction "A_1") (pintype "passive"))
      (node (ref "Q1") (pin "5") (pinfunction "D1_5") (pintype "passive"))
      (node (ref "Q2") (pin "5") (pinfunction "D1_5") (pintype "passive"))
      (node (ref "Q3") (pin "5") (pinfunction "D1_5") (pintype "passive"))
      (node (ref "R1") (pin "1") (pinfunction "1_1") (pintype "passive"))
      (node (ref "R18") (pin "1") (pinfunction "1_1") (pintype "passive"))
      (node (ref "R9") (pin "1") (pinfunction "1_1") (pintype "passive"))
    )
    (net (code "51") (name "unconnected-(U1-DT-Pad21)") (class "Default")
      (node (ref "U1") (pin "21") (pinfunction "DT_21") (pintype "input+no_connect"))
    )
    (net (code "52") (name "unconnected-(U1-MODE-Pad5)") (class "Default")
      (node (ref "U1") (pin "5") (pinfunction "MODE_5") (pintype "input+no_connect"))
    )
    (net (code "53") (name "unconnected-(U1-NC-Pad7)") (class "Default")
      (node (ref "U1") (pin "7") (pinfunction "NC_7") (pintype "passive+no_connect"))
    )
    (net (code "54") (name "unconnected-(U1-NC-Pad8)") (class "Default")
      (node (ref "U1") (pin "8") (pinfunction "NC_8") (pintype "passive+no_connect"))
    )
  )
)
